# Multimode-VCF-LM13600_old.net
KiCad netlist of a schematic drawn in EAGLE
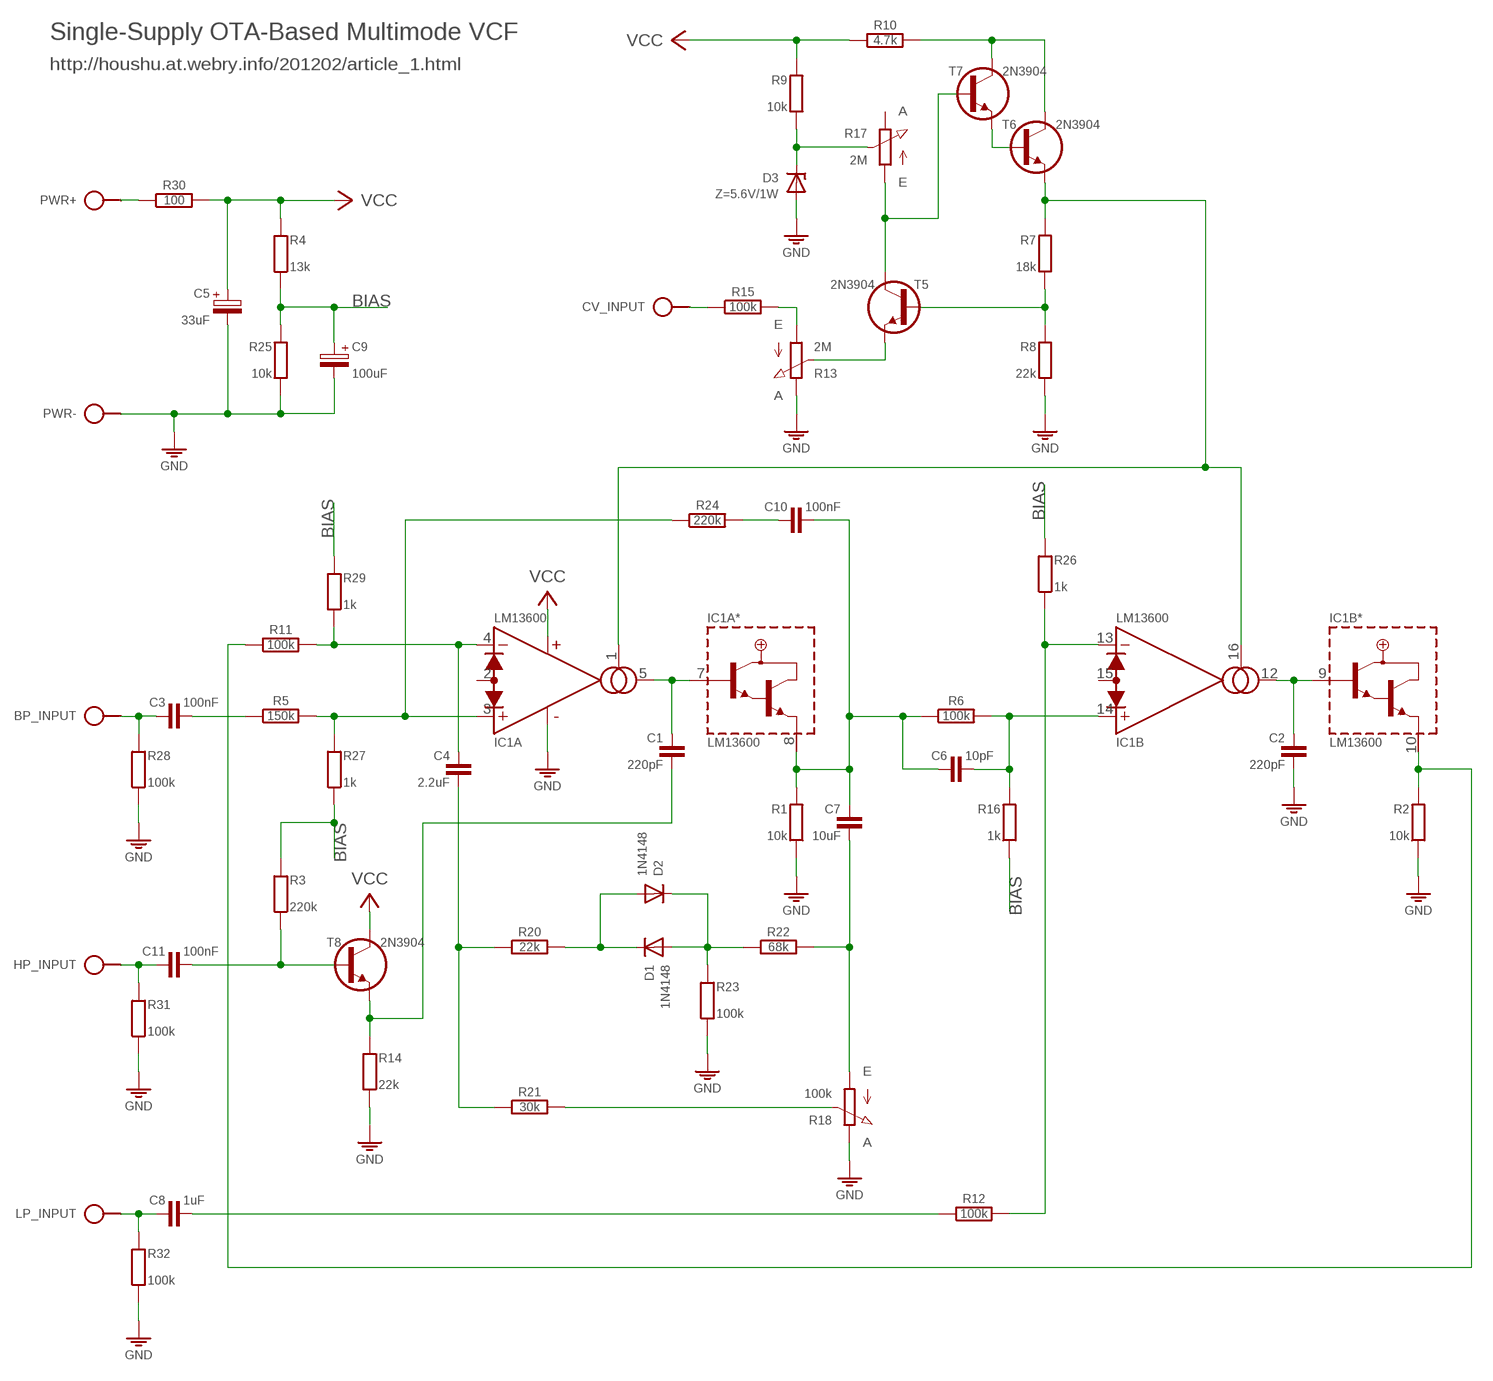
[diagram p0: schematic, sheet 1]

(export (version "E")
  (design (tool "Eeschema 10.0.6"))
  (components
    (comp (ref "BP_INPUT")
      (value "SPAD")
      (footprint "eagle-import:SPAD")
      (libsource (lib "eagle-import") (part "SPAD"))
    )
    (comp (ref "C1")
      (value "220pF")
      (footprint "eagle-import:C050-020X036_V")
      (libsource (lib "eagle-import") (part "C050-020X036/V"))
    )
    (comp (ref "C2")
      (value "220pF")
      (footprint "eagle-import:C050-020X036_V")
      (libsource (lib "eagle-import") (part "C050-020X036/V"))
    )
    (comp (ref "C3")
      (value "100nF")
      (footprint "eagle-import:C050-020X044")
      (libsource (lib "eagle-import") (part "C-H050-020X044"))
    )
    (comp (ref "C4")
      (value "2.2uF")
      (footprint "eagle-import:C050-024X044_V")
      (libsource (lib "eagle-import") (part "C050-024X044/V"))
    )
    (comp (ref "C5")
      (value "33uF")
      (footprint "eagle-import:E2.5-4_V")
      (libsource (lib "eagle-import") (part "CPOLE2,5-4/V"))
    )
    (comp (ref "C6")
      (value "10pF")
      (footprint "eagle-import:C050-020X036")
      (libsource (lib "eagle-import") (part "C-H050-020X036"))
    )
    (comp (ref "C7")
      (value "10uF")
      (footprint "eagle-import:C050-020X036_V")
      (libsource (lib "eagle-import") (part "C050-020X036/V"))
    )
    (comp (ref "C8")
      (value "1uF")
      (footprint "eagle-import:C050-024X044")
      (libsource (lib "eagle-import") (part "C-H050-024X044"))
    )
    (comp (ref "C9")
      (value "100uF")
      (footprint "eagle-import:E2.5-4_V")
      (libsource (lib "eagle-import") (part "CPOLE2,5-4/V"))
    )
    (comp (ref "C10")
      (value "100nF")
      (footprint "eagle-import:C050-020X044")
      (libsource (lib "eagle-import") (part "C-H050-020X044"))
    )
    (comp (ref "C11")
      (value "100nF")
      (footprint "eagle-import:C050-020X044_V")
      (libsource (lib "eagle-import") (part "C-H050-020X044/V"))
    )
    (comp (ref "CV_INPUT")
      (value "SPAD")
      (footprint "eagle-import:SPAD")
      (libsource (lib "eagle-import") (part "SPAD"))
    )
    (comp (ref "D1")
      (value "1N4148")
      (footprint "eagle-import:DO34-2,5-A")
      (libsource (lib "eagle-import") (part "1N414834-2,5-A"))
    )
    (comp (ref "D2")
      (value "1N4148")
      (footprint "eagle-import:DO34-2,5")
      (libsource (lib "eagle-import") (part "1N414834-2,5"))
    )
    (comp (ref "D3")
      (value "Z=5.6V/1W")
      (footprint "eagle-import:DO35Z7_V")
      (libsource (lib "eagle-import") (part "Z-DIODE-35Z7/V"))
    )
    (comp (ref "HP_INPUT")
      (value "SPAD")
      (footprint "eagle-import:SPAD")
      (libsource (lib "eagle-import") (part "SPAD"))
    )
    (comp (ref "IC1")
      (value "LM13600")
      (footprint "eagle-import:DIL16")
      (libsource (lib "eagle-import") (part "LM13600"))
    )
    (comp (ref "LP_INPUT")
      (value "SPAD")
      (footprint "eagle-import:SPAD")
      (libsource (lib "eagle-import") (part "SPAD"))
    )
    (comp (ref "PWR")
      (value "SPAD+--+")
      (footprint "eagle-import:SPAD-+")
      (libsource (lib "eagle-import") (part "SPAD+--+"))
    )
    (comp (ref "R1")
      (value "10k")
      (footprint "eagle-import:0204_10-V")
      (libsource (lib "eagle-import") (part "R0204/10-V"))
    )
    (comp (ref "R2")
      (value "10k")
      (footprint "eagle-import:0204_10")
      (libsource (lib "eagle-import") (part "R0204/10"))
    )
    (comp (ref "R3")
      (value "220k")
      (footprint "eagle-import:0204_10-V")
      (libsource (lib "eagle-import") (part "R0204/10-V"))
    )
    (comp (ref "R4")
      (value "13k")
      (footprint "eagle-import:0204_10-V")
      (libsource (lib "eagle-import") (part "R0204/10-V"))
    )
    (comp (ref "R5")
      (value "150k")
      (footprint "eagle-import:0204_10")
      (libsource (lib "eagle-import") (part "R-H0204/10"))
    )
    (comp (ref "R6")
      (value "100k")
      (footprint "eagle-import:0204_7-V")
      (libsource (lib "eagle-import") (part "R-H0204/7-V"))
    )
    (comp (ref "R7")
      (value "18k")
      (footprint "eagle-import:0204_10-V")
      (libsource (lib "eagle-import") (part "R0204/10-V"))
    )
    (comp (ref "R8")
      (value "22k")
      (footprint "eagle-import:0204_10-V")
      (libsource (lib "eagle-import") (part "R0204/10-V"))
    )
    (comp (ref "R9")
      (value "10k")
      (footprint "eagle-import:0204_10-V")
      (libsource (lib "eagle-import") (part "R0204/10-V"))
    )
    (comp (ref "R10")
      (value "4.7k")
      (footprint "eagle-import:0204_10")
      (libsource (lib "eagle-import") (part "R-H0204/10"))
    )
    (comp (ref "R11")
      (value "100k")
      (footprint "eagle-import:0204_10")
      (libsource (lib "eagle-import") (part "R-H0204/10"))
    )
    (comp (ref "R12")
      (value "100k")
      (footprint "eagle-import:0204_10")
      (libsource (lib "eagle-import") (part "R-H0204/10"))
    )
    (comp (ref "R13")
      (value "2M")
      (footprint "eagle-import:POT-V")
      (libsource (lib "eagle-import") (part "POT-V"))
    )
    (comp (ref "R14")
      (value "22k")
      (footprint "eagle-import:0204_10-V")
      (libsource (lib "eagle-import") (part "R0204/10-V"))
    )
    (comp (ref "R15")
      (value "100k")
      (footprint "eagle-import:0204_10")
      (libsource (lib "eagle-import") (part "R-H0204/10"))
    )
    (comp (ref "R16")
      (value "1k")
      (footprint "eagle-import:0204_7-V")
      (libsource (lib "eagle-import") (part "R0204/7-V"))
    )
    (comp (ref "R17")
      (value "2M")
      (footprint "eagle-import:POT-V")
      (libsource (lib "eagle-import") (part "POT-V"))
    )
    (comp (ref "R18")
      (value "100k")
      (footprint "eagle-import:POT")
      (libsource (lib "eagle-import") (part "POT"))
    )
    (comp (ref "R20")
      (value "22k")
      (footprint "eagle-import:0204_10")
      (libsource (lib "eagle-import") (part "R-H0204/10"))
    )
    (comp (ref "R21")
      (value "30k")
      (footprint "eagle-import:0204_10")
      (libsource (lib "eagle-import") (part "R-H0204/10"))
    )
    (comp (ref "R22")
      (value "68k")
      (footprint "eagle-import:0204_10")
      (libsource (lib "eagle-import") (part "R-H0204/10"))
    )
    (comp (ref "R23")
      (value "100k")
      (footprint "eagle-import:0204_10-V")
      (libsource (lib "eagle-import") (part "R0204/10-V"))
    )
    (comp (ref "R24")
      (value "220k")
      (footprint "eagle-import:0204_10-V")
      (libsource (lib "eagle-import") (part "R-H0204/10-V"))
    )
    (comp (ref "R25")
      (value "10k")
      (footprint "eagle-import:0204_10-V")
      (libsource (lib "eagle-import") (part "R0204/10-V"))
    )
    (comp (ref "R26")
      (value "1k")
      (footprint "eagle-import:0204_7")
      (libsource (lib "eagle-import") (part "R0204/7"))
    )
    (comp (ref "R27")
      (value "1k")
      (footprint "eagle-import:0204_10-V")
      (libsource (lib "eagle-import") (part "R0204/10-V"))
    )
    (comp (ref "R28")
      (value "100k")
      (footprint "eagle-import:0204_10-V")
      (libsource (lib "eagle-import") (part "R0204/10-V"))
    )
    (comp (ref "R29")
      (value "1k")
      (footprint "eagle-import:0204_10-V")
      (libsource (lib "eagle-import") (part "R0204/10-V"))
    )
    (comp (ref "R30")
      (value "100")
      (footprint "eagle-import:0204_10")
      (libsource (lib "eagle-import") (part "R-H0204/10"))
    )
    (comp (ref "R31")
      (value "100k")
      (footprint "eagle-import:0204_10-V")
      (libsource (lib "eagle-import") (part "R0204/10-V"))
    )
    (comp (ref "R32")
      (value "100k")
      (footprint "eagle-import:0204_10-V")
      (libsource (lib "eagle-import") (part "R0204/10-V"))
    )
    (comp (ref "T5")
      (value "2N3904")
      (footprint "eagle-import:TO92")
      (libsource (lib "eagle-import") (part "2N3904"))
    )
    (comp (ref "T6")
      (value "2N3904")
      (footprint "eagle-import:TO92")
      (libsource (lib "eagle-import") (part "2N3904"))
    )
    (comp (ref "T7")
      (value "2N3904")
      (footprint "eagle-import:TO92")
      (libsource (lib "eagle-import") (part "2N3904"))
    )
    (comp (ref "T8")
      (value "2N3904")
      (footprint "eagle-import:TO92")
      (libsource (lib "eagle-import") (part "2N3904"))
    )
  )
  (nets
    (net (code "1") (name "/BIAS") (class "Default")
      (node (ref "C9") (pin "+") (pinfunction "+_+") (pintype "passive"))
      (node (ref "R16") (pin "1") (pinfunction "2_1") (pintype "passive"))
      (node (ref "R25") (pin "1") (pinfunction "1_1") (pintype "passive"))
      (node (ref "R26") (pin "2") (pinfunction "1_2") (pintype "passive"))
      (node (ref "R27") (pin "2") (pinfunction "2_2") (pintype "passive"))
      (node (ref "R29") (pin "1") (pinfunction "1_1") (pintype "passive"))
      (node (ref "R3") (pin "1") (pinfunction "1_1") (pintype "passive"))
      (node (ref "R4") (pin "2") (pinfunction "2_2") (pintype "passive"))
    )
    (net (code "2") (name "GND") (class "Default")
      (node (ref "C2") (pin "2") (pinfunction "2_2") (pintype "passive"))
      (node (ref "C5") (pin "-") (pinfunction "-_-") (pintype "passive"))
      (node (ref "C9") (pin "-") (pinfunction "-_-") (pintype "passive"))
      (node (ref "D3") (pin "A") (pinfunction "A_A") (pintype "passive"))
      (node (ref "IC1") (pin "6") (pinfunction "V-_6") (pintype "power_in"))
      (node (ref "PWR") (pin "1") (pinfunction "P$1_1") (pintype "passive"))
      (node (ref "R1") (pin "2") (pinfunction "2_2") (pintype "passive"))
      (node (ref "R13") (pin "E") (pinfunction "E_E") (pintype "passive"))
      (node (ref "R14") (pin "2") (pinfunction "2_2") (pintype "passive"))
      (node (ref "R18") (pin "3") (pinfunction "E_3") (pintype "passive"))
      (node (ref "R2") (pin "1") (pinfunction "2_1") (pintype "passive"))
      (node (ref "R23") (pin "2") (pinfunction "2_2") (pintype "passive"))
      (node (ref "R25") (pin "2") (pinfunction "2_2") (pintype "passive"))
      (node (ref "R28") (pin "2") (pinfunction "2_2") (pintype "passive"))
      (node (ref "R31") (pin "2") (pinfunction "2_2") (pintype "passive"))
      (node (ref "R32") (pin "2") (pinfunction "2_2") (pintype "passive"))
      (node (ref "R8") (pin "2") (pinfunction "2_2") (pintype "passive"))
    )
    (net (code "3") (name "Net-(BP_INPUT-P$1)") (class "Default")
      (node (ref "BP_INPUT") (pin "1") (pinfunction "P$1_1") (pintype "passive"))
      (node (ref "C3") (pin "1") (pinfunction "1_1") (pintype "passive"))
      (node (ref "R28") (pin "1") (pinfunction "1_1") (pintype "passive"))
    )
    (net (code "4") (name "Net-(C3-Pad2)") (class "Default")
      (node (ref "C3") (pin "2") (pinfunction "2_2") (pintype "passive"))
      (node (ref "R5") (pin "1") (pinfunction "1_1") (pintype "passive"))
    )
    (net (code "5") (name "Net-(C4-Pad2)") (class "Default")
      (node (ref "C4") (pin "2") (pinfunction "2_2") (pintype "passive"))
      (node (ref "R20") (pin "1") (pinfunction "1_1") (pintype "passive"))
      (node (ref "R21") (pin "1") (pinfunction "1_1") (pintype "passive"))
    )
    (net (code "6") (name "Net-(C8-Pad2)") (class "Default")
      (node (ref "C8") (pin "2") (pinfunction "2_2") (pintype "passive"))
      (node (ref "R12") (pin "1") (pinfunction "1_1") (pintype "passive"))
    )
    (net (code "7") (name "Net-(C10-Pad1)") (class "Default")
      (node (ref "C10") (pin "1") (pinfunction "1_1") (pintype "passive"))
      (node (ref "R24") (pin "2") (pinfunction "2_2") (pintype "passive"))
    )
    (net (code "8") (name "Net-(CV_INPUT-P$1)") (class "Default")
      (node (ref "CV_INPUT") (pin "1") (pinfunction "P$1_1") (pintype "passive"))
      (node (ref "R15") (pin "1") (pinfunction "1_1") (pintype "passive"))
    )
    (net (code "9") (name "Net-(D1-PadA)") (class "Default")
      (node (ref "D1") (pin "A") (pinfunction "A_A") (pintype "passive"))
      (node (ref "D2") (pin "C") (pinfunction "C_C") (pintype "passive"))
      (node (ref "R22") (pin "1") (pinfunction "1_1") (pintype "passive"))
      (node (ref "R23") (pin "1") (pinfunction "1_1") (pintype "passive"))
    )
    (net (code "10") (name "Net-(D1-PadC)") (class "Default")
      (node (ref "D1") (pin "C") (pinfunction "C_C") (pintype "passive"))
      (node (ref "D2") (pin "A") (pinfunction "A_A") (pintype "passive"))
      (node (ref "R20") (pin "2") (pinfunction "2_2") (pintype "passive"))
    )
    (net (code "11") (name "Net-(D3-PadC)") (class "Default")
      (node (ref "D3") (pin "C") (pinfunction "C_C") (pintype "passive"))
      (node (ref "R17") (pin "S") (pinfunction "S_S") (pintype "passive"))
      (node (ref "R9") (pin "2") (pinfunction "2_2") (pintype "passive"))
    )
    (net (code "12") (name "Net-(HP_INPUT-P$1)") (class "Default")
      (node (ref "C11") (pin "1") (pinfunction "1_1") (pintype "passive"))
      (node (ref "HP_INPUT") (pin "1") (pinfunction "P$1_1") (pintype "passive"))
      (node (ref "R31") (pin "1") (pinfunction "1_1") (pintype "passive"))
    )
    (net (code "13") (name "Net-(IC1B-+IN)") (class "Default")
      (node (ref "IC1") (pin "3") (pinfunction "+IN_3") (pintype "input"))
      (node (ref "R24") (pin "1") (pinfunction "1_1") (pintype "passive"))
      (node (ref "R27") (pin "1") (pinfunction "1_1") (pintype "passive"))
      (node (ref "R5") (pin "2") (pinfunction "2_2") (pintype "passive"))
    )
    (net (code "14") (name "Net-(IC1B--IN)") (class "Default")
      (node (ref "C4") (pin "1") (pinfunction "1_1") (pintype "passive"))
      (node (ref "IC1") (pin "4") (pinfunction "-IN_4") (pintype "input"))
      (node (ref "R11") (pin "2") (pinfunction "2_2") (pintype "passive"))
      (node (ref "R29") (pin "2") (pinfunction "2_2") (pintype "passive"))
    )
    (net (code "15") (name "Net-(IC1B-AMP{slash}BIAS)") (class "Default")
      (node (ref "IC1") (pin "1") (pinfunction "AMP/BIAS_1") (pintype "input"))
      (node (ref "IC1") (pin "16") (pinfunction "AMP/BIAS_16") (pintype "input"))
      (node (ref "R7") (pin "1") (pinfunction "1_1") (pintype "passive"))
      (node (ref "T6") (pin "1") (pinfunction "E_1") (pintype "passive"))
    )
    (net (code "16") (name "Net-(IC1B-OUT)") (class "Default")
      (node (ref "C1") (pin "1") (pinfunction "1_1") (pintype "passive"))
      (node (ref "IC1") (pin "5") (pinfunction "OUT_5") (pintype "output"))
      (node (ref "IC1") (pin "7") (pinfunction "BUFF/IN_7") (pintype "input"))
    )
    (net (code "17") (name "Net-(IC1C-BUFF{slash}OUT)") (class "Default")
      (node (ref "C10") (pin "2") (pinfunction "2_2") (pintype "passive"))
      (node (ref "C6") (pin "1") (pinfunction "1_1") (pintype "passive"))
      (node (ref "C7") (pin "1") (pinfunction "1_1") (pintype "passive"))
      (node (ref "IC1") (pin "8") (pinfunction "BUFF/OUT_8") (pintype "output"))
      (node (ref "R1") (pin "1") (pinfunction "1_1") (pintype "passive"))
      (node (ref "R6") (pin "1") (pinfunction "1_1") (pintype "passive"))
    )
    (net (code "18") (name "Net-(IC1D-+IN)") (class "Default")
      (node (ref "C6") (pin "2") (pinfunction "2_2") (pintype "passive"))
      (node (ref "IC1") (pin "14") (pinfunction "+IN_14") (pintype "input"))
      (node (ref "R16") (pin "2") (pinfunction "1_2") (pintype "passive"))
      (node (ref "R6") (pin "2") (pinfunction "2_2") (pintype "passive"))
    )
    (net (code "19") (name "Net-(IC1D--IN)") (class "Default")
      (node (ref "IC1") (pin "13") (pinfunction "-IN_13") (pintype "input"))
      (node (ref "R12") (pin "2") (pinfunction "2_2") (pintype "passive"))
      (node (ref "R26") (pin "1") (pinfunction "2_1") (pintype "passive"))
    )
    (net (code "20") (name "Net-(IC1D-OUT)") (class "Default")
      (node (ref "C2") (pin "1") (pinfunction "1_1") (pintype "passive"))
      (node (ref "IC1") (pin "12") (pinfunction "OUT_12") (pintype "output"))
      (node (ref "IC1") (pin "9") (pinfunction "BUFF/IN_9") (pintype "input"))
    )
    (net (code "21") (name "Net-(IC1E-BUFF{slash}OUT)") (class "Default")
      (node (ref "IC1") (pin "10") (pinfunction "BUFF/OUT_10") (pintype "output"))
      (node (ref "R11") (pin "1") (pinfunction "1_1") (pintype "passive"))
      (node (ref "R2") (pin "2") (pinfunction "1_2") (pintype "passive"))
    )
    (net (code "22") (name "Net-(LP_INPUT-P$1)") (class "Default")
      (node (ref "C8") (pin "1") (pinfunction "1_1") (pintype "passive"))
      (node (ref "LP_INPUT") (pin "1") (pinfunction "P$1_1") (pintype "passive"))
      (node (ref "R32") (pin "1") (pinfunction "1_1") (pintype "passive"))
    )
    (net (code "23") (name "Net-(PWRA-P$1)") (class "Default")
      (node (ref "PWR") (pin "2") (pinfunction "P$1_2") (pintype "passive"))
      (node (ref "R30") (pin "1") (pinfunction "1_1") (pintype "passive"))
    )
    (net (code "24") (name "Net-(R13-PadA)") (class "Default")
      (node (ref "R13") (pin "A") (pinfunction "A_A") (pintype "passive"))
      (node (ref "R15") (pin "2") (pinfunction "2_2") (pintype "passive"))
    )
    (net (code "25") (name "Net-(R18-A)") (class "Default")
      (node (ref "C7") (pin "2") (pinfunction "2_2") (pintype "passive"))
      (node (ref "R18") (pin "1") (pinfunction "A_1") (pintype "passive"))
      (node (ref "R22") (pin "2") (pinfunction "2_2") (pintype "passive"))
    )
    (net (code "26") (name "Net-(R18-S)") (class "Default")
      (node (ref "R18") (pin "2") (pinfunction "S_2") (pintype "passive"))
      (node (ref "R21") (pin "2") (pinfunction "2_2") (pintype "passive"))
    )
    (net (code "27") (name "Net-(T5-B)") (class "Default")
      (node (ref "R7") (pin "2") (pinfunction "2_2") (pintype "passive"))
      (node (ref "R8") (pin "1") (pinfunction "1_1") (pintype "passive"))
      (node (ref "T5") (pin "2") (pinfunction "B_2") (pintype "passive"))
    )
    (net (code "28") (name "Net-(T5-C)") (class "Default")
      (node (ref "R17") (pin "A") (pinfunction "A_A") (pintype "passive"))
      (node (ref "T5") (pin "3") (pinfunction "C_3") (pintype "passive"))
      (node (ref "T7") (pin "2") (pinfunction "B_2") (pintype "passive"))
    )
    (net (code "29") (name "Net-(T5-E)") (class "Default")
      (node (ref "R13") (pin "S") (pinfunction "S_S") (pintype "passive"))
      (node (ref "T5") (pin "1") (pinfunction "E_1") (pintype "passive"))
    )
    (net (code "30") (name "Net-(T6-B)") (class "Default")
      (node (ref "T6") (pin "2") (pinfunction "B_2") (pintype "passive"))
      (node (ref "T7") (pin "1") (pinfunction "E_1") (pintype "passive"))
    )
    (net (code "31") (name "Net-(T6-C)") (class "Default")
      (node (ref "R10") (pin "2") (pinfunction "2_2") (pintype "passive"))
      (node (ref "T6") (pin "3") (pinfunction "C_3") (pintype "passive"))
      (node (ref "T7") (pin "3") (pinfunction "C_3") (pintype "passive"))
    )
    (net (code "32") (name "Net-(T8-B)") (class "Default")
      (node (ref "C11") (pin "2") (pinfunction "2_2") (pintype "passive"))
      (node (ref "R3") (pin "2") (pinfunction "2_2") (pintype "passive"))
      (node (ref "T8") (pin "2") (pinfunction "B_2") (pintype "passive"))
    )
    (net (code "33") (name "Net-(T8-E)") (class "Default")
      (node (ref "C1") (pin "2") (pinfunction "2_2") (pintype "passive"))
      (node (ref "R14") (pin "1") (pinfunction "1_1") (pintype "passive"))
      (node (ref "T8") (pin "1") (pinfunction "E_1") (pintype "passive"))
    )
    (net (code "34") (name "VCC") (class "Default")
      (node (ref "C5") (pin "+") (pinfunction "+_+") (pintype "passive"))
      (node (ref "IC1") (pin "11") (pinfunction "V+_11") (pintype "power_in"))
      (node (ref "R10") (pin "1") (pinfunction "1_1") (pintype "passive"))
      (node (ref "R30") (pin "2") (pinfunction "2_2") (pintype "passive"))
      (node (ref "R4") (pin "1") (pinfunction "1_1") (pintype "passive"))
      (node (ref "R9") (pin "1") (pinfunction "1_1") (pintype "passive"))
      (node (ref "T8") (pin "3") (pinfunction "C_3") (pintype "passive"))
    )
    (net (code "35") (name "unconnected-(IC1B-DIODE{slash}BIAS-Pad2)") (class "Default")
      (node (ref "IC1") (pin "2") (pinfunction "DIODE/BIAS_2") (pintype "input"))
    )
    (net (code "36") (name "unconnected-(IC1D-DIODE{slash}BIAS-Pad15)") (class "Default")
      (node (ref "IC1") (pin "15") (pinfunction "DIODE/BIAS_15") (pintype "input"))
    )
    (net (code "37") (name "unconnected-(R17-PadE)") (class "Default")
      (node (ref "R17") (pin "E") (pinfunction "E_E") (pintype "passive"))
    )
  )
)
